# revision1-has-mistakes.net
KiCad netlist of a schematic drawn in EAGLE
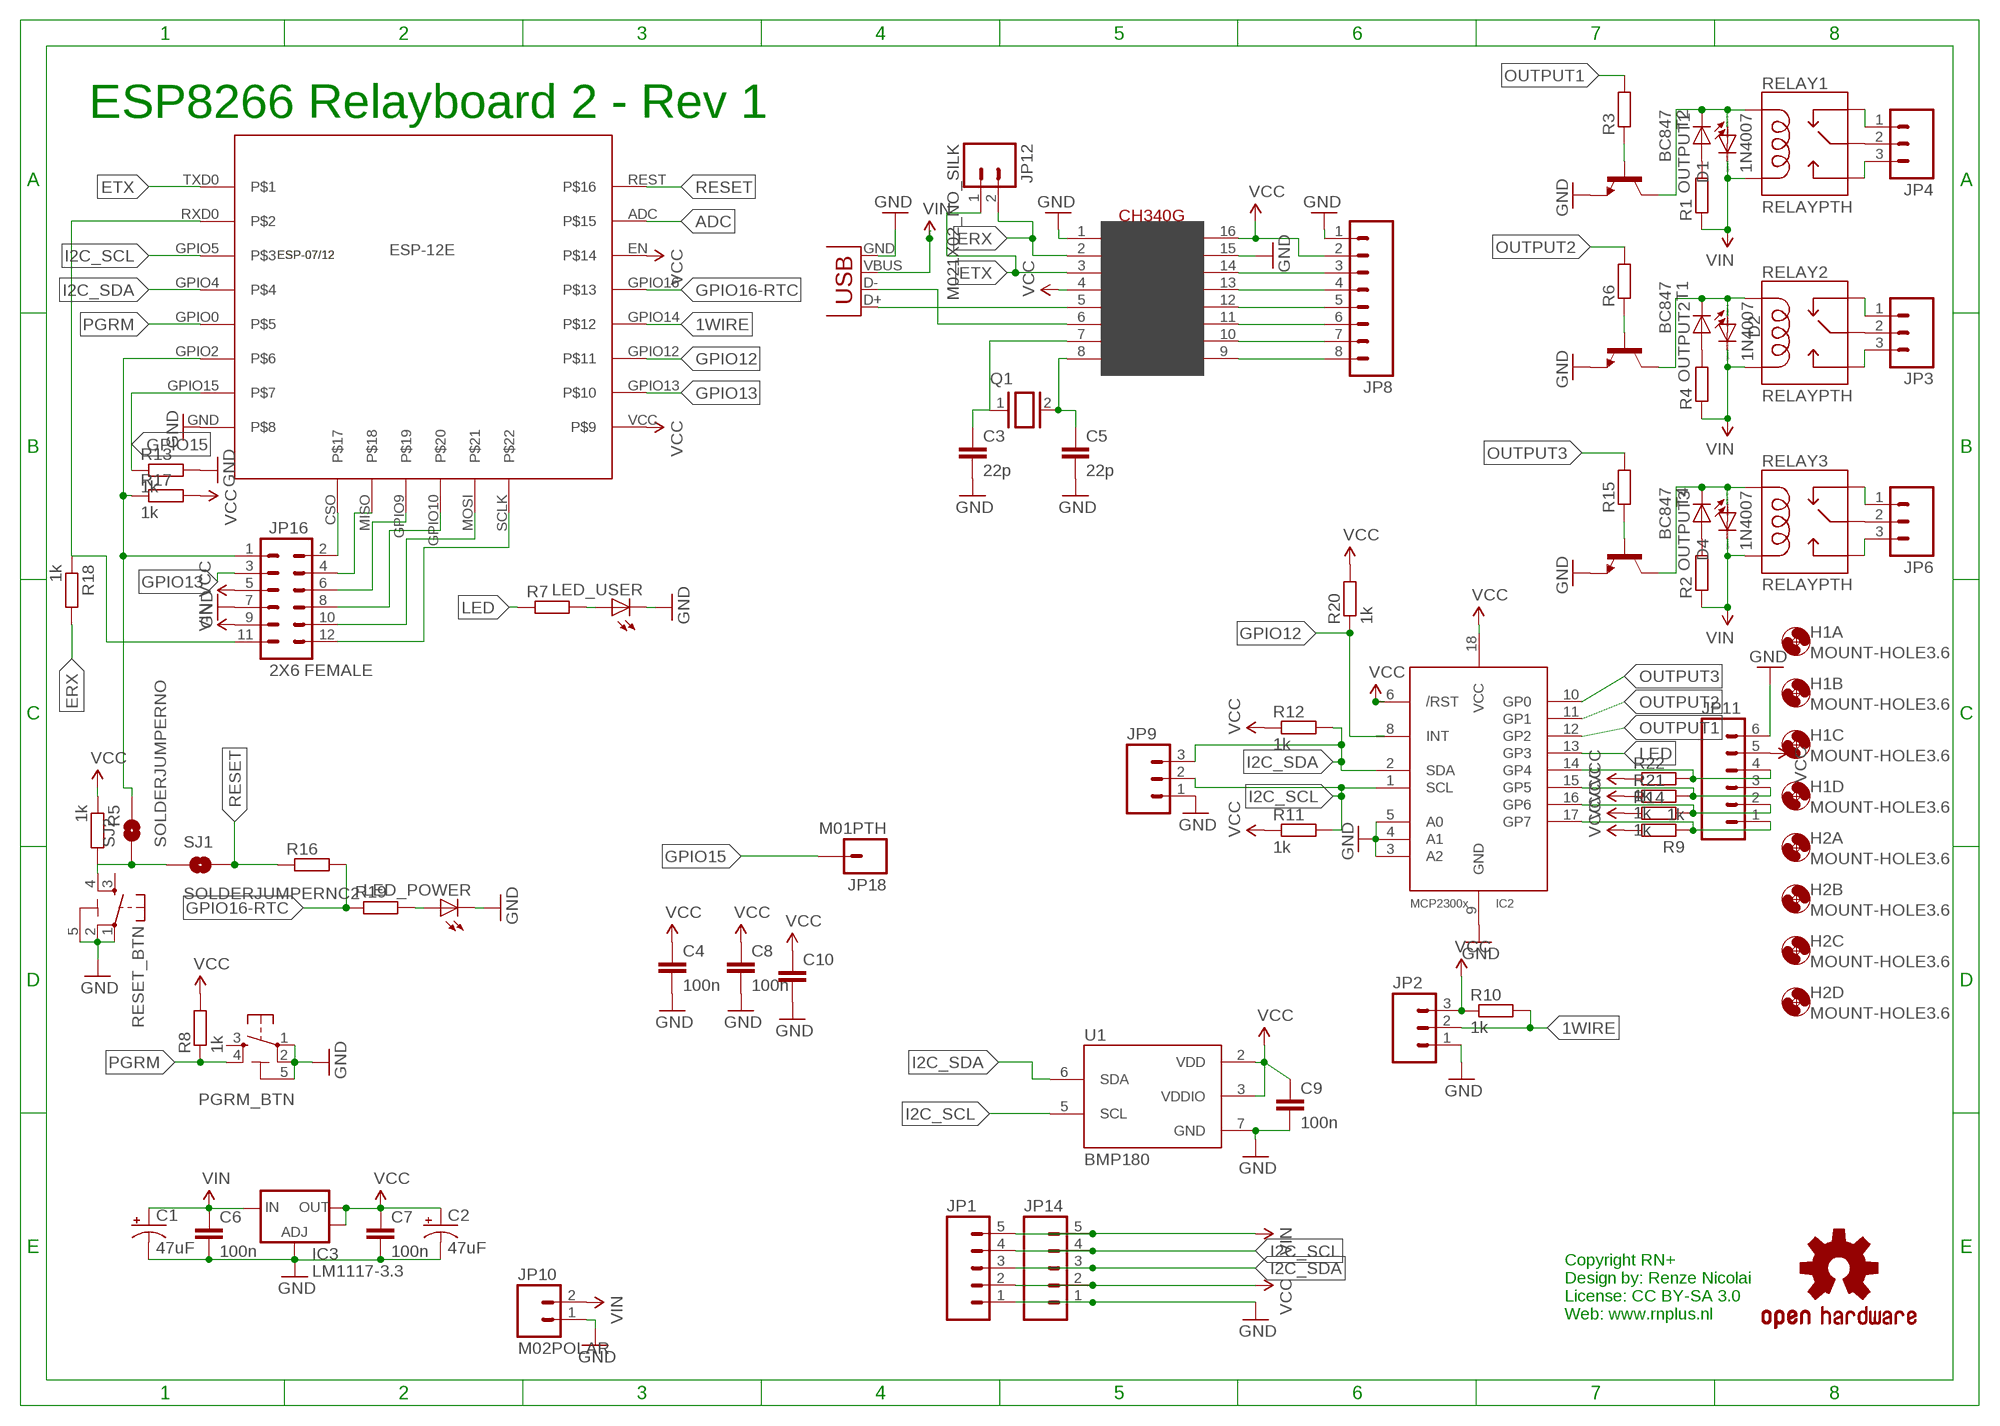
[diagram p0: schematic, sheet 1]

(export (version "E")
  (design (tool "Eeschema 10.0.6"))
  (components
    (comp (ref "C1")
      (value "47uF")
      (footprint "eagle-import:PANASONIC_D")
      (libsource (lib "eagle-import") (part "CAP_POLD"))
    )
    (comp (ref "C2")
      (value "47uF")
      (footprint "eagle-import:PANASONIC_D")
      (libsource (lib "eagle-import") (part "CAP_POLD"))
    )
    (comp (ref "C3")
      (value "22p")
      (footprint "eagle-import:C0805K")
      (libsource (lib "eagle-import") (part "C-EUC0805K"))
    )
    (comp (ref "C4")
      (value "100n")
      (footprint "eagle-import:C0805K")
      (libsource (lib "eagle-import") (part "C-EUC0805K"))
    )
    (comp (ref "C5")
      (value "22p")
      (footprint "eagle-import:C0805K")
      (libsource (lib "eagle-import") (part "C-EUC0805K"))
    )
    (comp (ref "C6")
      (value "100n")
      (footprint "eagle-import:C0805K")
      (libsource (lib "eagle-import") (part "C-EUC0805K"))
    )
    (comp (ref "C7")
      (value "100n")
      (footprint "eagle-import:C0805K")
      (libsource (lib "eagle-import") (part "C-EUC0805K"))
    )
    (comp (ref "C8")
      (value "100n")
      (footprint "eagle-import:C0805K")
      (libsource (lib "eagle-import") (part "C-EUC0805K"))
    )
    (comp (ref "C9")
      (value "100n")
      (footprint "eagle-import:C0805K")
      (libsource (lib "eagle-import") (part "C-EUC0805K"))
    )
    (comp (ref "C10")
      (value "C-EUC0805K")
      (footprint "eagle-import:C0805K")
      (libsource (lib "eagle-import") (part "C-EUC0805K"))
    )
    (comp (ref "D1")
      (value "1N4942")
      (footprint "eagle-import:DO41-10")
      (libsource (lib "eagle-import") (part "1N4942"))
    )
    (comp (ref "D2")
      (value "1N4942")
      (footprint "eagle-import:DO41-10")
      (libsource (lib "eagle-import") (part "1N4942"))
    )
    (comp (ref "D4")
      (value "1N4942")
      (footprint "eagle-import:DO41-10")
      (libsource (lib "eagle-import") (part "1N4942"))
    )
    (comp (ref "H1A")
      (value "MOUNT-HOLE3.6")
      (footprint "eagle-import:3,6")
      (libsource (lib "eagle-import") (part "MOUNT-HOLE3.6"))
    )
    (comp (ref "H1B")
      (value "MOUNT-HOLE3.6")
      (footprint "eagle-import:3,6")
      (libsource (lib "eagle-import") (part "MOUNT-HOLE3.6"))
    )
    (comp (ref "H1C")
      (value "MOUNT-HOLE3.6")
      (footprint "eagle-import:3,6")
      (libsource (lib "eagle-import") (part "MOUNT-HOLE3.6"))
    )
    (comp (ref "H1D")
      (value "MOUNT-HOLE3.6")
      (footprint "eagle-import:3,6")
      (libsource (lib "eagle-import") (part "MOUNT-HOLE3.6"))
    )
    (comp (ref "H2A")
      (value "MOUNT-HOLE3.6")
      (footprint "eagle-import:3,6")
      (libsource (lib "eagle-import") (part "MOUNT-HOLE3.6"))
    )
    (comp (ref "H2B")
      (value "MOUNT-HOLE3.6")
      (footprint "eagle-import:3,6")
      (libsource (lib "eagle-import") (part "MOUNT-HOLE3.6"))
    )
    (comp (ref "H2C")
      (value "MOUNT-HOLE3.6")
      (footprint "eagle-import:3,6")
      (libsource (lib "eagle-import") (part "MOUNT-HOLE3.6"))
    )
    (comp (ref "H2D")
      (value "MOUNT-HOLE3.6")
      (footprint "eagle-import:3,6")
      (libsource (lib "eagle-import") (part "MOUNT-HOLE3.6"))
    )
    (comp (ref "IC2")
      (value "MCP23008/SO")
      (footprint "eagle-import:SO18W")
      (libsource (lib "eagle-import") (part "MCP23008/SO"))
    )
    (comp (ref "IC3")
      (value "LM1117-3.3")
      (footprint "eagle-import:SOT223")
      (libsource (lib "eagle-import") (part "V_REG_LM1117SOT223"))
    )
    (comp (ref "JP1")
      (value "M05PTH")
      (footprint "eagle-import:1X05")
      (libsource (lib "eagle-import") (part "M05PTH"))
    )
    (comp (ref "JP2")
      (value "M03LONGPADS")
      (footprint "eagle-import:1X03_LONGPADS")
      (libsource (lib "eagle-import") (part "M03LONGPADS"))
    )
    (comp (ref "JP3")
      (value "M03-SCREW-5MM")
      (footprint "eagle-import:SCREWTERMINAL-5MM-3")
      (libsource (lib "eagle-import") (part "M03-SCREW-5MM"))
    )
    (comp (ref "JP4")
      (value "M03-SCREW-5MM")
      (footprint "eagle-import:SCREWTERMINAL-5MM-3")
      (libsource (lib "eagle-import") (part "M03-SCREW-5MM"))
    )
    (comp (ref "JP5")
      (value "USB-B")
      (footprint "eagle-import:USB-B-PTH")
      (libsource (lib "eagle-import") (part "USBPTH"))
    )
    (comp (ref "JP6")
      (value "M03-SCREW-5MM")
      (footprint "eagle-import:SCREWTERMINAL-5MM-3")
      (libsource (lib "eagle-import") (part "M03-SCREW-5MM"))
    )
    (comp (ref "JP8")
      (value "M08SILK_FEMALE_PTH")
      (footprint "eagle-import:1X08")
      (libsource (lib "eagle-import") (part "M08SILK_FEMALE_PTH"))
    )
    (comp (ref "JP9")
      (value "M031X03_NO_SILK")
      (footprint "eagle-import:1X03_NO_SILK")
      (libsource (lib "eagle-import") (part "M031X03_NO_SILK"))
    )
    (comp (ref "JP10")
      (value "M02POLAR")
      (footprint "eagle-import:MOLEX-1X2")
      (libsource (lib "eagle-import") (part "M02POLAR"))
    )
    (comp (ref "JP11")
      (value "M06LONGPADS")
      (footprint "eagle-import:1X06_LONGPADS")
      (libsource (lib "eagle-import") (part "M06LONGPADS"))
    )
    (comp (ref "JP12")
      (value "M021X02_NO_SILK")
      (footprint "eagle-import:1X02_NO_SILK")
      (libsource (lib "eagle-import") (part "M021X02_NO_SILK"))
    )
    (comp (ref "JP14")
      (value "M05PTH")
      (footprint "eagle-import:1X05")
      (libsource (lib "eagle-import") (part "M05PTH"))
    )
    (comp (ref "JP16")
      (value "2X6 FEMALE")
      (footprint "eagle-import:2X6")
      (libsource (lib "eagle-import") (part "M06X2PTH_FEMALE"))
    )
    (comp (ref "JP18")
      (value "M01PTH")
      (footprint "eagle-import:1X01")
      (libsource (lib "eagle-import") (part "M01PTH"))
    )
    (comp (ref "LED_POWER")
      (value "LEDCHIP-LED0805")
      (footprint "eagle-import:CHIP-LED0805")
      (libsource (lib "eagle-import") (part "LEDCHIP-LED0805"))
    )
    (comp (ref "LED_USER")
      (value "LEDCHIP-LED0805")
      (footprint "eagle-import:CHIP-LED0805")
      (libsource (lib "eagle-import") (part "LEDCHIP-LED0805"))
    )
    (comp (ref "LOGO1")
      (value "OSHW-LOGOL")
      (footprint "eagle-import:OSHW-LOGO-L")
      (libsource (lib "eagle-import") (part "OSHW-LOGOL"))
    )
    (comp (ref "OUTPUT1")
      (value "LEDCHIP-LED0805")
      (footprint "eagle-import:CHIP-LED0805")
      (libsource (lib "eagle-import") (part "LEDCHIP-LED0805"))
    )
    (comp (ref "OUTPUT2")
      (value "LEDCHIP-LED0805")
      (footprint "eagle-import:CHIP-LED0805")
      (libsource (lib "eagle-import") (part "LEDCHIP-LED0805"))
    )
    (comp (ref "OUTPUT3")
      (value "LEDCHIP-LED0805")
      (footprint "eagle-import:CHIP-LED0805")
      (libsource (lib "eagle-import") (part "LEDCHIP-LED0805"))
    )
    (comp (ref "PGRM_BTN")
      (value "SMARTPRJ_TS42")
      (footprint "eagle-import:SMARTPRJ_TS42")
      (libsource (lib "eagle-import") (part "SMARTPRJ_TS42"))
    )
    (comp (ref "Q1")
      (value "XTAL/S")
      (footprint "eagle-import:QS")
      (libsource (lib "eagle-import") (part "XTAL/S"))
    )
    (comp (ref "R1")
      (value "SMARTPRJ_R-EU_M0805")
      (footprint "eagle-import:SMARTPRJ_M0805")
      (libsource (lib "eagle-import") (part "SMARTPRJ_R-EU_M0805"))
    )
    (comp (ref "R2")
      (value "SMARTPRJ_R-EU_M0805")
      (footprint "eagle-import:SMARTPRJ_M0805")
      (libsource (lib "eagle-import") (part "SMARTPRJ_R-EU_M0805"))
    )
    (comp (ref "R3")
      (value "SMARTPRJ_R-EU_M0805")
      (footprint "eagle-import:SMARTPRJ_M0805")
      (libsource (lib "eagle-import") (part "SMARTPRJ_R-EU_M0805"))
    )
    (comp (ref "R4")
      (value "SMARTPRJ_R-EU_M0805")
      (footprint "eagle-import:SMARTPRJ_M0805")
      (libsource (lib "eagle-import") (part "SMARTPRJ_R-EU_M0805"))
    )
    (comp (ref "R5")
      (value "1k")
      (footprint "eagle-import:SMARTPRJ_M0805")
      (libsource (lib "eagle-import") (part "SMARTPRJ_R-EU_M0805"))
    )
    (comp (ref "R6")
      (value "SMARTPRJ_R-EU_M0805")
      (footprint "eagle-import:SMARTPRJ_M0805")
      (libsource (lib "eagle-import") (part "SMARTPRJ_R-EU_M0805"))
    )
    (comp (ref "R7")
      (value "SMARTPRJ_R-EU_M0805")
      (footprint "eagle-import:SMARTPRJ_M0805")
      (libsource (lib "eagle-import") (part "SMARTPRJ_R-EU_M0805"))
    )
    (comp (ref "R8")
      (value "1k")
      (footprint "eagle-import:SMARTPRJ_M0805")
      (libsource (lib "eagle-import") (part "SMARTPRJ_R-EU_M0805"))
    )
    (comp (ref "R9")
      (value "1k")
      (footprint "eagle-import:SMARTPRJ_M0805")
      (libsource (lib "eagle-import") (part "SMARTPRJ_R-EU_M0805"))
    )
    (comp (ref "R10")
      (value "1k")
      (footprint "eagle-import:SMARTPRJ_M0805")
      (libsource (lib "eagle-import") (part "SMARTPRJ_R-EU_M0805"))
    )
    (comp (ref "R11")
      (value "1k")
      (footprint "eagle-import:SMARTPRJ_M0805")
      (libsource (lib "eagle-import") (part "SMARTPRJ_R-EU_M0805"))
    )
    (comp (ref "R12")
      (value "1k")
      (footprint "eagle-import:SMARTPRJ_M0805")
      (libsource (lib "eagle-import") (part "SMARTPRJ_R-EU_M0805"))
    )
    (comp (ref "R13")
      (value "1k")
      (footprint "eagle-import:SMARTPRJ_M0805")
      (libsource (lib "eagle-import") (part "SMARTPRJ_R-EU_M0805"))
    )
    (comp (ref "R14")
      (value "1k")
      (footprint "eagle-import:SMARTPRJ_M0805")
      (libsource (lib "eagle-import") (part "SMARTPRJ_R-EU_M0805"))
    )
    (comp (ref "R15")
      (value "SMARTPRJ_R-EU_M0805")
      (footprint "eagle-import:SMARTPRJ_M0805")
      (libsource (lib "eagle-import") (part "SMARTPRJ_R-EU_M0805"))
    )
    (comp (ref "R16")
      (value "SMARTPRJ_R-EU_M0805")
      (footprint "eagle-import:SMARTPRJ_M0805")
      (libsource (lib "eagle-import") (part "SMARTPRJ_R-EU_M0805"))
    )
    (comp (ref "R17")
      (value "1k")
      (footprint "eagle-import:SMARTPRJ_M0805")
      (libsource (lib "eagle-import") (part "SMARTPRJ_R-EU_M0805"))
    )
    (comp (ref "R18")
      (value "1k")
      (footprint "eagle-import:SMARTPRJ_M0805")
      (libsource (lib "eagle-import") (part "SMARTPRJ_R-EU_M0805"))
    )
    (comp (ref "R19")
      (value "SMARTPRJ_R-EU_M0805")
      (footprint "eagle-import:SMARTPRJ_M0805")
      (libsource (lib "eagle-import") (part "SMARTPRJ_R-EU_M0805"))
    )
    (comp (ref "R20")
      (value "1k")
      (footprint "eagle-import:SMARTPRJ_M0805")
      (libsource (lib "eagle-import") (part "SMARTPRJ_R-EU_M0805"))
    )
    (comp (ref "R21")
      (value "1k")
      (footprint "eagle-import:SMARTPRJ_M0805")
      (libsource (lib "eagle-import") (part "SMARTPRJ_R-EU_M0805"))
    )
    (comp (ref "R22")
      (value "1k")
      (footprint "eagle-import:SMARTPRJ_M0805")
      (libsource (lib "eagle-import") (part "SMARTPRJ_R-EU_M0805"))
    )
    (comp (ref "RELAY1")
      (value "RELAYPTH")
      (footprint "eagle-import:SRD-05VDC-SL-C")
      (libsource (lib "eagle-import") (part "RELAYPTH"))
    )
    (comp (ref "RELAY2")
      (value "RELAYPTH")
      (footprint "eagle-import:SRD-05VDC-SL-C")
      (libsource (lib "eagle-import") (part "RELAYPTH"))
    )
    (comp (ref "RELAY3")
      (value "RELAYPTH")
      (footprint "eagle-import:SRD-05VDC-SL-C")
      (libsource (lib "eagle-import") (part "RELAYPTH"))
    )
    (comp (ref "RESET_BTN")
      (value "SMARTPRJ_TS42")
      (footprint "eagle-import:SMARTPRJ_TS42")
      (libsource (lib "eagle-import") (part "SMARTPRJ_TS42"))
    )
    (comp (ref "SJ1")
      (value "SOLDERJUMPERNC2")
      (footprint "eagle-import:SJ_2S-NOTRACE")
      (libsource (lib "eagle-import") (part "SOLDERJUMPERNC2"))
    )
    (comp (ref "SJ2")
      (value "SOLDERJUMPERNO")
      (footprint "eagle-import:SJ_2S-NO")
      (libsource (lib "eagle-import") (part "SOLDERJUMPERNO"))
    )
    (comp (ref "T1")
      (value "BC847")
      (footprint "eagle-import:SOT23")
      (libsource (lib "eagle-import") (part "BC847"))
    )
    (comp (ref "T2")
      (value "BC847")
      (footprint "eagle-import:SOT23")
      (libsource (lib "eagle-import") (part "BC847"))
    )
    (comp (ref "T4")
      (value "BC847")
      (footprint "eagle-import:SOT23")
      (libsource (lib "eagle-import") (part "BC847"))
    )
    (comp (ref "U$1")
      (value "CH340G")
      (footprint "eagle-import:SOIC16")
      (libsource (lib "eagle-import") (part "CH340G"))
    )
    (comp (ref "U$2")
      (value "ESP-07/12_ESP-12E")
      (footprint "eagle-import:ESP-07_12")
      (libsource (lib "eagle-import") (part "ESP-07/12_ESP-12E"))
    )
    (comp (ref "U1")
      (value "BMP180")
      (footprint "eagle-import:BMP180")
      (libsource (lib "eagle-import") (part "BMP180"))
    )
  )
  (nets
    (net (code "1") (name "1WIRE") (class "Default")
      (node (ref "JP2") (pin "2") (pinfunction "2_2") (pintype "passive"))
      (node (ref "R10") (pin "2") (pinfunction "2_2") (pintype "passive"))
      (node (ref "U$2") (pin "GPIO14") (pinfunction "P$12_GPIO14") (pintype "bidirectional"))
    )
    (net (code "2") (name "ADC") (class "Default")
      (node (ref "U$2") (pin "ADC") (pinfunction "P$15_ADC") (pintype "bidirectional"))
    )
    (net (code "3") (name "ERX") (class "Default")
      (node (ref "JP12") (pin "2") (pinfunction "2_2") (pintype "passive"))
      (node (ref "R18") (pin "2") (pinfunction "2_2") (pintype "passive"))
      (node (ref "U$1") (pin "2") (pinfunction "TX_2") (pintype "bidirectional"))
    )
    (net (code "4") (name "ETX") (class "Default")
      (node (ref "JP12") (pin "1") (pinfunction "1_1") (pintype "passive"))
      (node (ref "U$1") (pin "3") (pinfunction "RX_3") (pintype "bidirectional"))
      (node (ref "U$2") (pin "TXD0") (pinfunction "P$1_TXD0") (pintype "bidirectional"))
    )
    (net (code "5") (name "GND") (class "Default")
      (node (ref "C1") (pin "-") (pinfunction "-_-") (pintype "passive"))
      (node (ref "C10") (pin "2") (pinfunction "2_2") (pintype "passive"))
      (node (ref "C2") (pin "-") (pinfunction "-_-") (pintype "passive"))
      (node (ref "C3") (pin "2") (pinfunction "2_2") (pintype "passive"))
      (node (ref "C4") (pin "2") (pinfunction "2_2") (pintype "passive"))
      (node (ref "C5") (pin "2") (pinfunction "2_2") (pintype "passive"))
      (node (ref "C6") (pin "2") (pinfunction "2_2") (pintype "passive"))
      (node (ref "C7") (pin "2") (pinfunction "2_2") (pintype "passive"))
      (node (ref "C8") (pin "2") (pinfunction "2_2") (pintype "passive"))
      (node (ref "C9") (pin "2") (pinfunction "2_2") (pintype "passive"))
      (node (ref "IC2") (pin "3") (pinfunction "A2_3") (pintype "input"))
      (node (ref "IC2") (pin "4") (pinfunction "A1_4") (pintype "input"))
      (node (ref "IC2") (pin "5") (pinfunction "A0_5") (pintype "input"))
      (node (ref "IC2") (pin "9") (pinfunction "GND_9") (pintype "power_in"))
      (node (ref "IC3") (pin "1") (pinfunction "ADJ_1") (pintype "input"))
      (node (ref "JP1") (pin "1") (pinfunction "1_1") (pintype "passive"))
      (node (ref "JP10") (pin "1") (pinfunction "1_1") (pintype "passive"))
      (node (ref "JP11") (pin "6") (pinfunction "6_6") (pintype "passive"))
      (node (ref "JP14") (pin "1") (pinfunction "1_1") (pintype "passive"))
      (node (ref "JP16") (pin "7") (pinfunction "7_7") (pintype "passive"))
      (node (ref "JP2") (pin "1") (pinfunction "1_1") (pintype "passive"))
      (node (ref "JP5") (pin "GND") (pinfunction "GND_GND") (pintype "bidirectional"))
      (node (ref "JP8") (pin "1") (pinfunction "1_1") (pintype "passive"))
      (node (ref "JP9") (pin "1") (pinfunction "1_1") (pintype "passive"))
      (node (ref "LED_POWER") (pin "C") (pinfunction "C_C") (pintype "passive"))
      (node (ref "LED_USER") (pin "C") (pinfunction "C_C") (pintype "passive"))
      (node (ref "PGRM_BTN") (pin "1") (pinfunction "1_1") (pintype "passive"))
      (node (ref "PGRM_BTN") (pin "2") (pinfunction "2_2") (pintype "passive"))
      (node (ref "PGRM_BTN") (pin "5") (pinfunction "5-GND_5") (pintype "power_in"))
      (node (ref "R13") (pin "2") (pinfunction "2_2") (pintype "passive"))
      (node (ref "RESET_BTN") (pin "1") (pinfunction "1_1") (pintype "passive"))
      (node (ref "RESET_BTN") (pin "2") (pinfunction "2_2") (pintype "passive"))
      (node (ref "RESET_BTN") (pin "5") (pinfunction "5-GND_5") (pintype "power_in"))
      (node (ref "T1") (pin "2") (pinfunction "E_2") (pintype "passive"))
      (node (ref "T2") (pin "2") (pinfunction "E_2") (pintype "passive"))
      (node (ref "T4") (pin "2") (pinfunction "E_2") (pintype "passive"))
      (node (ref "U$1") (pin "1") (pinfunction "GND_1") (pintype "bidirectional"))
      (node (ref "U$1") (pin "15") (pinfunction "RS232_15") (pintype "bidirectional"))
      (node (ref "U$2") (pin "GND") (pinfunction "P$8_GND") (pintype "bidirectional"))
      (node (ref "U1") (pin "7") (pinfunction "GND_7") (pintype "power_in"))
    )
    (net (code "6") (name "GPIO12") (class "Default")
      (node (ref "IC2") (pin "8") (pinfunction "INT_8") (pintype "output"))
      (node (ref "R20") (pin "1") (pinfunction "1_1") (pintype "passive"))
      (node (ref "U$2") (pin "GPIO12") (pinfunction "P$11_GPIO12") (pintype "bidirectional"))
    )
    (net (code "7") (name "GPIO13") (class "Default")
      (node (ref "JP16") (pin "3") (pinfunction "3_3") (pintype "passive"))
      (node (ref "U$2") (pin "GPIO13") (pinfunction "P$10_GPIO13") (pintype "bidirectional"))
    )
    (net (code "8") (name "GPIO15") (class "Default")
      (node (ref "JP18") (pin "1") (pinfunction "1_1") (pintype "passive"))
      (node (ref "R13") (pin "1") (pinfunction "1_1") (pintype "passive"))
      (node (ref "U$2") (pin "GPIO15") (pinfunction "P$7_GPIO15") (pintype "bidirectional"))
    )
    (net (code "9") (name "GPIO16-RTC") (class "Default")
      (node (ref "R16") (pin "2") (pinfunction "2_2") (pintype "passive"))
      (node (ref "R19") (pin "1") (pinfunction "1_1") (pintype "passive"))
      (node (ref "U$2") (pin "GPIO16") (pinfunction "P$13_GPIO16") (pintype "bidirectional"))
    )
    (net (code "10") (name "I2C_SCL") (class "Default")
      (node (ref "IC2") (pin "1") (pinfunction "SCL_1") (pintype "bidirectional"))
      (node (ref "JP1") (pin "4") (pinfunction "4_4") (pintype "passive"))
      (node (ref "JP14") (pin "4") (pinfunction "4_4") (pintype "passive"))
      (node (ref "JP9") (pin "2") (pinfunction "2_2") (pintype "passive"))
      (node (ref "R11") (pin "2") (pinfunction "2_2") (pintype "passive"))
      (node (ref "U$2") (pin "GPIO5") (pinfunction "P$3_GPIO5") (pintype "bidirectional"))
      (node (ref "U1") (pin "5") (pinfunction "SCL_5") (pintype "input"))
    )
    (net (code "11") (name "I2C_SDA") (class "Default")
      (node (ref "IC2") (pin "2") (pinfunction "SDA_2") (pintype "bidirectional"))
      (node (ref "JP1") (pin "3") (pinfunction "3_3") (pintype "passive"))
      (node (ref "JP14") (pin "3") (pinfunction "3_3") (pintype "passive"))
      (node (ref "JP9") (pin "3") (pinfunction "3_3") (pintype "passive"))
      (node (ref "R12") (pin "2") (pinfunction "2_2") (pintype "passive"))
      (node (ref "U$2") (pin "GPIO4") (pinfunction "P$4_GPIO4") (pintype "bidirectional"))
      (node (ref "U1") (pin "6") (pinfunction "SDA_6") (pintype "bidirectional"))
    )
    (net (code "12") (name "LED") (class "Default")
      (node (ref "IC2") (pin "13") (pinfunction "GP3_13") (pintype "bidirectional"))
      (node (ref "R7") (pin "1") (pinfunction "1_1") (pintype "passive"))
    )
    (net (code "13") (name "Net-(IC2-GP4)") (class "Default")
      (node (ref "IC2") (pin "14") (pinfunction "GP4_14") (pintype "bidirectional"))
      (node (ref "JP11") (pin "4") (pinfunction "4_4") (pintype "passive"))
      (node (ref "R22") (pin "2") (pinfunction "2_2") (pintype "passive"))
    )
    (net (code "14") (name "Net-(IC2-GP5)") (class "Default")
      (node (ref "IC2") (pin "15") (pinfunction "GP5_15") (pintype "bidirectional"))
      (node (ref "JP11") (pin "3") (pinfunction "3_3") (pintype "passive"))
      (node (ref "R21") (pin "2") (pinfunction "2_2") (pintype "passive"))
    )
    (net (code "15") (name "Net-(IC2-GP6)") (class "Default")
      (node (ref "IC2") (pin "16") (pinfunction "GP6_16") (pintype "bidirectional"))
      (node (ref "JP11") (pin "2") (pinfunction "2_2") (pintype "passive"))
      (node (ref "R14") (pin "2") (pinfunction "2_2") (pintype "passive"))
    )
    (net (code "16") (name "Net-(IC2-GP7)") (class "Default")
      (node (ref "IC2") (pin "17") (pinfunction "GP7_17") (pintype "bidirectional"))
      (node (ref "JP11") (pin "1") (pinfunction "1_1") (pintype "passive"))
      (node (ref "R9") (pin "1") (pinfunction "1_1") (pintype "passive"))
    )
    (net (code "17") (name "Net-(JP3-Pad2)") (class "Default")
      (node (ref "JP3") (pin "2") (pinfunction "2_2") (pintype "passive"))
      (node (ref "RELAY2") (pin "SWCOMMON") (pinfunction "SWCOMMON_SWCOMMON") (pintype "bidirectional"))
    )
    (net (code "18") (name "Net-(JP3-Pad3)") (class "Default")
      (node (ref "JP3") (pin "3") (pinfunction "3_3") (pintype "passive"))
      (node (ref "RELAY2") (pin "SWOPEN") (pinfunction "SWOPEN_SWOPEN") (pintype "bidirectional"))
    )
    (net (code "19") (name "Net-(JP4-Pad2)") (class "Default")
      (node (ref "JP4") (pin "2") (pinfunction "2_2") (pintype "passive"))
      (node (ref "RELAY1") (pin "SWCOMMON") (pinfunction "SWCOMMON_SWCOMMON") (pintype "bidirectional"))
    )
    (net (code "20") (name "Net-(JP4-Pad3)") (class "Default")
      (node (ref "JP4") (pin "3") (pinfunction "3_3") (pintype "passive"))
      (node (ref "RELAY1") (pin "SWOPEN") (pinfunction "SWOPEN_SWOPEN") (pintype "bidirectional"))
    )
    (net (code "21") (name "Net-(JP6-Pad2)") (class "Default")
      (node (ref "JP6") (pin "2") (pinfunction "2_2") (pintype "passive"))
      (node (ref "RELAY3") (pin "SWCOMMON") (pinfunction "SWCOMMON_SWCOMMON") (pintype "bidirectional"))
    )
    (net (code "22") (name "Net-(JP6-Pad3)") (class "Default")
      (node (ref "JP6") (pin "3") (pinfunction "3_3") (pintype "passive"))
      (node (ref "RELAY3") (pin "SWOPEN") (pinfunction "SWOPEN_SWOPEN") (pintype "bidirectional"))
    )
    (net (code "23") (name "Net-(LED_POWER-PadA)") (class "Default")
      (node (ref "LED_POWER") (pin "A") (pinfunction "A_A") (pintype "passive"))
      (node (ref "R19") (pin "2") (pinfunction "2_2") (pintype "passive"))
    )
    (net (code "24") (name "Net-(LED_USER-PadA)") (class "Default")
      (node (ref "LED_USER") (pin "A") (pinfunction "A_A") (pintype "passive"))
      (node (ref "R7") (pin "2") (pinfunction "2_2") (pintype "passive"))
    )
    (net (code "25") (name "Net-(OUTPUT1-PadA)") (class "Default")
      (node (ref "OUTPUT1") (pin "A") (pinfunction "A_A") (pintype "passive"))
      (node (ref "R1") (pin "2") (pinfunction "2_2") (pintype "passive"))
    )
    (net (code "26") (name "Net-(OUTPUT2-PadA)") (class "Default")
      (node (ref "OUTPUT2") (pin "A") (pinfunction "A_A") (pintype "passive"))
      (node (ref "R4") (pin "2") (pinfunction "2_2") (pintype "passive"))
    )
    (net (code "27") (name "Net-(OUTPUT3-PadA)") (class "Default")
      (node (ref "OUTPUT3") (pin "A") (pinfunction "A_A") (pintype "passive"))
      (node (ref "R2") (pin "2") (pinfunction "2_2") (pintype "passive"))
    )
    (net (code "28") (name "Net-(R5-Pad2)") (class "Default")
      (node (ref "R5") (pin "2") (pinfunction "2_2") (pintype "passive"))
      (node (ref "RESET_BTN") (pin "4") (pinfunction "4_4") (pintype "passive"))
      (node (ref "SJ1") (pin "1") (pinfunction "1_1") (pintype "passive"))
      (node (ref "SJ2") (pin "1") (pinfunction "1_1") (pintype "passive"))
    )
    (net (code "29") (name "Net-(RELAY1-SWCLOSE)") (class "Default")
      (node (ref "JP4") (pin "1") (pinfunction "1_1") (pintype "passive"))
      (node (ref "RELAY1") (pin "SWCLOSED") (pinfunction "SWCLOSE_SWCLOSED") (pintype "bidirectional"))
    )
    (net (code "30") (name "Net-(RELAY2-SWCLOSE)") (class "Default")
      (node (ref "JP3") (pin "1") (pinfunction "1_1") (pintype "passive"))
      (node (ref "RELAY2") (pin "SWCLOSED") (pinfunction "SWCLOSE_SWCLOSED") (pintype "bidirectional"))
    )
    (net (code "31") (name "Net-(RELAY3-SWCLOSE)") (class "Default")
      (node (ref "JP6") (pin "1") (pinfunction "1_1") (pintype "passive"))
      (node (ref "RELAY3") (pin "SWCLOSED") (pinfunction "SWCLOSE_SWCLOSED") (pintype "bidirectional"))
    )
    (net (code "32") (name "Net-(T1-B)") (class "Default")
      (node (ref "R6") (pin "1") (pinfunction "1_1") (pintype "passive"))
      (node (ref "T1") (pin "1") (pinfunction "B_1") (pintype "passive"))
    )
    (net (code "33") (name "Net-(T1-C)") (class "Default")
      (node (ref "D2") (pin "A") (pinfunction "A_A") (pintype "passive"))
      (node (ref "OUTPUT2") (pin "C") (pinfunction "C_C") (pintype "passive"))
      (node (ref "RELAY2") (pin "COIL1") (pinfunction "COIL1_COIL1") (pintype "bidirectional"))
      (node (ref "T1") (pin "3") (pinfunction "C_3") (pintype "passive"))
    )
    (net (code "34") (name "Net-(T2-B)") (class "Default")
      (node (ref "R3") (pin "1") (pinfunction "1_1") (pintype "passive"))
      (node (ref "T2") (pin "1") (pinfunction "B_1") (pintype "passive"))
    )
    (net (code "35") (name "Net-(T2-C)") (class "Default")
      (node (ref "D1") (pin "A") (pinfunction "A_A") (pintype "passive"))
      (node (ref "OUTPUT1") (pin "C") (pinfunction "C_C") (pintype "passive"))
      (node (ref "RELAY1") (pin "COIL1") (pinfunction "COIL1_COIL1") (pintype "bidirectional"))
      (node (ref "T2") (pin "3") (pinfunction "C_3") (pintype "passive"))
    )
    (net (code "36") (name "Net-(T4-B)") (class "Default")
      (node (ref "R15") (pin "1") (pinfunction "1_1") (pintype "passive"))
      (node (ref "T4") (pin "1") (pinfunction "B_1") (pintype "passive"))
    )
    (net (code "37") (name "Net-(T4-C)") (class "Default")
      (node (ref "D4") (pin "A") (pinfunction "A_A") (pintype "passive"))
      (node (ref "OUTPUT3") (pin "C") (pinfunction "C_C") (pintype "passive"))
      (node (ref "RELAY3") (pin "COIL1") (pinfunction "COIL1_COIL1") (pintype "bidirectional"))
      (node (ref "T4") (pin "3") (pinfunction "C_3") (pintype "passive"))
    )
    (net (code "38") (name "Net-(U$1-CTS)") (class "Default")
      (node (ref "JP8") (pin "8") (pinfunction "8_8") (pintype "passive"))
      (node (ref "U$1") (pin "9") (pinfunction "CTS_9") (pintype "bidirectional"))
    )
    (net (code "39") (name "Net-(U$1-D+)") (class "Default")
      (node (ref "JP5") (pin "D+") (pinfunction "D+_D+") (pintype "bidirectional"))
      (node (ref "U$1") (pin "5") (pinfunction "D+_5") (pintype "bidirectional"))
    )
    (net (code "40") (name "Net-(U$1-D-)") (class "Default")
      (node (ref "JP5") (pin "D-") (pinfunction "D-_D-") (pintype "bidirectional"))
      (node (ref "U$1") (pin "6") (pinfunction "D-_6") (pintype "bidirectional"))
    )
    (net (code "41") (name "Net-(U$1-DCD)") (class "Default")
      (node (ref "JP8") (pin "5") (pinfunction "5_5") (pintype "passive"))
      (node (ref "U$1") (pin "12") (pinfunction "DCD_12") (pintype "bidirectional"))
    )
    (net (code "42") (name "Net-(U$1-DSR)") (class "Default")
      (node (ref "JP8") (pin "7") (pinfunction "7_7") (pintype "passive"))
      (node (ref "U$1") (pin "10") (pinfunction "DSR_10") (pintype "bidirectional"))
    )
    (net (code "43") (name "Net-(U$1-DTR)") (class "Default")
      (node (ref "JP8") (pin "4") (pinfunction "4_4") (pintype "passive"))
      (node (ref "U$1") (pin "13") (pinfunction "DTR_13") (pintype "bidirectional"))
    )
    (net (code "44") (name "Net-(U$1-RI)") (class "Default")
      (node (ref "JP8") (pin "6") (pinfunction "6_6") (pintype "passive"))
      (node (ref "U$1") (pin "11") (pinfunction "RI_11") (pintype "bidirectional"))
    )
    (net (code "45") (name "Net-(U$1-RTS)") (class "Default")
      (node (ref "JP8") (pin "3") (pinfunction "3_3") (pintype "passive"))
      (node (ref "U$1") (pin "14") (pinfunction "RTS_14") (pintype "bidirectional"))
    )
    (net (code "46") (name "Net-(U$1-XI)") (class "Default")
      (node (ref "C3") (pin "1") (pinfunction "1_1") (pintype "passive"))
      (node (ref "Q1") (pin "1") (pinfunction "1_1") (pintype "passive"))
      (node (ref "U$1") (pin "7") (pinfunction "XI_7") (pintype "bidirectional"))
    )
    (net (code "47") (name "Net-(U$1-XO)") (class "Default")
      (node (ref "C5") (pin "1") (pinfunction "1_1") (pintype "passive"))
      (node (ref "Q1") (pin "2") (pinfunction "2_2") (pintype "passive"))
      (node (ref "U$1") (pin "8") (pinfunction "XO_8") (pintype "bidirectional"))
    )
    (net (code "48") (name "Net-(U$2-P$2)") (class "Default")
      (node (ref "JP16") (pin "11") (pinfunction "11_11") (pintype "passive"))
      (node (ref "R18") (pin "1") (pinfunction "1_1") (pintype "passive"))
      (node (ref "U$2") (pin "RXD0") (pinfunction "P$2_RXD0") (pintype "bidirectional"))
    )
    (net (code "49") (name "Net-(U$2-P$6)") (class "Default")
      (node (ref "JP16") (pin "1") (pinfunction "1_1") (pintype "passive"))
      (node (ref "R17") (pin "1") (pinfunction "1_1") (pintype "passive"))
      (node (ref "SJ2") (pin "2") (pinfunction "2_2") (pintype "passive"))
      (node (ref "U$2") (pin "GPIO2") (pinfunction "P$6_GPIO2") (pintype "bidirectional"))
    )
    (net (code "50") (name "Net-(U$2-P$17)") (class "Default")
      (node (ref "JP16") (pin "2") (pinfunction "2_2") (pintype "passive"))
      (node (ref "U$2") (pin "CSO") (pinfunction "P$17_CSO") (pintype "bidirectional"))
    )
    (net (code "51") (name "Net-(U$2-P$18)") (class "Default")
      (node (ref "JP16") (pin "4") (pinfunction "4_4") (pintype "passive"))
      (node (ref "U$2") (pin "MISO") (pinfunction "P$18_MISO") (pintype "bidirectional"))
    )
    (net (code "52") (name "Net-(U$2-P$19)") (class "Default")
      (node (ref "JP16") (pin "6") (pinfunction "6_6") (pintype "passive"))
      (node (ref "U$2") (pin "GPIO9") (pinfunction "P$19_GPIO9") (pintype "bidirectional"))
    )
    (net (code "53") (name "Net-(U$2-P$20)") (class "Default")
      (node (ref "JP16") (pin "8") (pinfunction "8_8") (pintype "passive"))
      (node (ref "U$2") (pin "GPIO10") (pinfunction "P$20_GPIO10") (pintype "bidirectional"))
    )
    (net (code "54") (name "Net-(U$2-P$21)") (class "Default")
      (node (ref "JP16") (pin "10") (pinfunction "10_10") (pintype "passive"))
      (node (ref "U$2") (pin "MOSI") (pinfunction "P$21_MOSI") (pintype "bidirectional"))
    )
    (net (code "55") (name "Net-(U$2-P$22)") (class "Default")
      (node (ref "JP16") (pin "12") (pinfunction "12_12") (pintype "passive"))
      (node (ref "U$2") (pin "SCLK") (pinfunction "P$22_SCLK") (pintype "bidirectional"))
    )
    (net (code "56") (name "OUTPUT1") (class "Default")
      (node (ref "IC2") (pin "12") (pinfunction "GP2_12") (pintype "bidirectional"))
      (node (ref "R3") (pin "2") (pinfunction "2_2") (pintype "passive"))
    )
    (net (code "57") (name "OUTPUT2") (class "Default")
      (node (ref "IC2") (pin "11") (pinfunction "GP1_11") (pintype "bidirectional"))
      (node (ref "R6") (pin "2") (pinfunction "2_2") (pintype "passive"))
    )
    (net (code "58") (name "OUTPUT3") (class "Default")
      (node (ref "IC2") (pin "10") (pinfunction "GP0_10") (pintype "bidirectional"))
      (node (ref "R15") (pin "2") (pinfunction "2_2") (pintype "passive"))
    )
    (net (code "59") (name "PGRM") (class "Default")
      (node (ref "PGRM_BTN") (pin "4") (pinfunction "4_4") (pintype "passive"))
      (node (ref "R8") (pin "1") (pinfunction "1_1") (pintype "passive"))
      (node (ref "U$2") (pin "GPIO0") (pinfunction "P$5_GPIO0") (pintype "bidirectional"))
    )
    (net (code "60") (name "RESET") (class "Default")
      (node (ref "R16") (pin "1") (pinfunction "1_1") (pintype "passive"))
      (node (ref "SJ1") (pin "2") (pinfunction "2_2") (pintype "passive"))
      (node (ref "U$2") (pin "REST") (pinfunction "P$16_REST") (pintype "bidirectional"))
    )
    (net (code "61") (name "VCC") (class "Default")
      (node (ref "C10") (pin "1") (pinfunction "1_1") (pintype "passive"))
      (node (ref "C2") (pin "+") (pinfunction "+_+") (pintype "passive"))
      (node (ref "C4") (pin "1") (pinfunction "1_1") (pintype "passive"))
      (node (ref "C7") (pin "1") (pinfunction "1_1") (pintype "passive"))
      (node (ref "C8") (pin "1") (pinfunction "1_1") (pintype "passive"))
      (node (ref "C9") (pin "1") (pinfunction "1_1") (pintype "passive"))
      (node (ref "IC2") (pin "18") (pinfunction "VCC_18") (pintype "power_in"))
      (node (ref "IC2") (pin "6") (pinfunction "/RST_6") (pintype "input"))
      (node (ref "IC3") (pin "2") (pinfunction "OUT_2") (pintype "output"))
      (node (ref "IC3") (pin "4") (pinfunction "OUT_4") (pintype "output"))
      (node (ref "JP1") (pin "2") (pinfunction "2_2") (pintype "passive"))
      (node (ref "JP11") (pin "5") (pinfunction "5_5") (pintype "passive"))
      (node (ref "JP14") (pin "2") (pinfunction "2_2") (pintype "passive"))
      (node (ref "JP16") (pin "5") (pinfunction "5_5") (pintype "passive"))
      (node (ref "JP2") (pin "3") (pinfunction "3_3") (pintype "passive"))
      (node (ref "JP8") (pin "2") (pinfunction "2_2") (pintype "passive"))
      (node (ref "R10") (pin "1") (pinfunction "1_1") (pintype "passive"))
      (node (ref "R11") (pin "1") (pinfunction "1_1") (pintype "passive"))
      (node (ref "R12") (pin "1") (pinfunction "1_1") (pintype "passive"))
      (node (ref "R14") (pin "1") (pinfunction "1_1") (pintype "passive"))
      (node (ref "R17") (pin "2") (pinfunction "2_2") (pintype "passive"))
      (node (ref "R20") (pin "2") (pinfunction "2_2") (pintype "passive"))
      (node (ref "R21") (pin "1") (pinfunction "1_1") (pintype "passive"))
      (node (ref "R22") (pin "1") (pinfunction "1_1") (pintype "passive"))
      (node (ref "R5") (pin "1") (pinfunction "1_1") (pintype "passive"))
      (node (ref "R8") (pin "2") (pinfunction "2_2") (pintype "passive"))
      (node (ref "R9") (pin "2") (pinfunction "2_2") (pintype "passive"))
      (node (ref "U$1") (pin "16") (pinfunction "VCC_16") (pintype "bidirectional"))
      (node (ref "U$1") (pin "4") (pinfunction "V3_4") (pintype "bidirectional"))
      (node (ref "U$2") (pin "EN") (pinfunction "P$14_EN") (pintype "bidirectional"))
      (node (ref "U$2") (pin "VCC") (pinfunction "P$9_VCC") (pintype "bidirectional"))
      (node (ref "U1") (pin "2") (pinfunction "VDD_2") (pintype "power_in"))
      (node (ref "U1") (pin "3") (pinfunction "VDDIO_3") (pintype "power_in"))
    )
    (net (code "62") (name "VIN") (class "Default")
      (node (ref "C1") (pin "+") (pinfunction "+_+") (pintype "passive"))
      (node (ref "C6") (pin "1") (pinfunction "1_1") (pintype "passive"))
      (node (ref "D1") (pin "C") (pinfunction "C_C") (pintype "passive"))
      (node (ref "D2") (pin "C") (pinfunction "C_C") (pintype "passive"))
      (node (ref "D4") (pin "C") (pinfunction "C_C") (pintype "passive"))
      (node (ref "IC3") (pin "3") (pinfunction "IN_3") (pintype "input"))
      (node (ref "JP1") (pin "5") (pinfunction "5_5") (pintype "passive"))
      (node (ref "JP10") (pin "2") (pinfunction "2_2") (pintype "passive"))
      (node (ref "JP14") (pin "5") (pinfunction "5_5") (pintype "passive"))
      (node (ref "JP16") (pin "9") (pinfunction "9_9") (pintype "passive"))
      (node (ref "JP5") (pin "VBUS") (pinfunction "VBUS_VBUS") (pintype "bidirectional"))
      (node (ref "R1") (pin "1") (pinfunction "1_1") (pintype "passive"))
      (node (ref "R2") (pin "1") (pinfunction "1_1") (pintype "passive"))
      (node (ref "R4") (pin "1") (pinfunction "1_1") (pintype "passive"))
      (node (ref "RELAY1") (pin "COIL0") (pinfunction "COIL0_COIL0") (pintype "bidirectional"))
      (node (ref "RELAY2") (pin "COIL0") (pinfunction "COIL0_COIL0") (pintype "bidirectional"))
      (node (ref "RELAY3") (pin "COIL0") (pinfunction "COIL0_COIL0") (pintype "bidirectional"))
    )
    (net (code "63") (name "unconnected-(PGRM_BTN-Pad3)") (class "Default")
      (node (ref "PGRM_BTN") (pin "3") (pinfunction "3_3") (pintype "passive"))
    )
    (net (code "64") (name "unconnected-(RESET_BTN-Pad3)") (class "Default")
      (node (ref "RESET_BTN") (pin "3") (pinfunction "3_3") (pintype "passive"))
    )
  )
)
